# Impedance_converter.net
KiCad netlist of a schematic drawn in Altium Designer
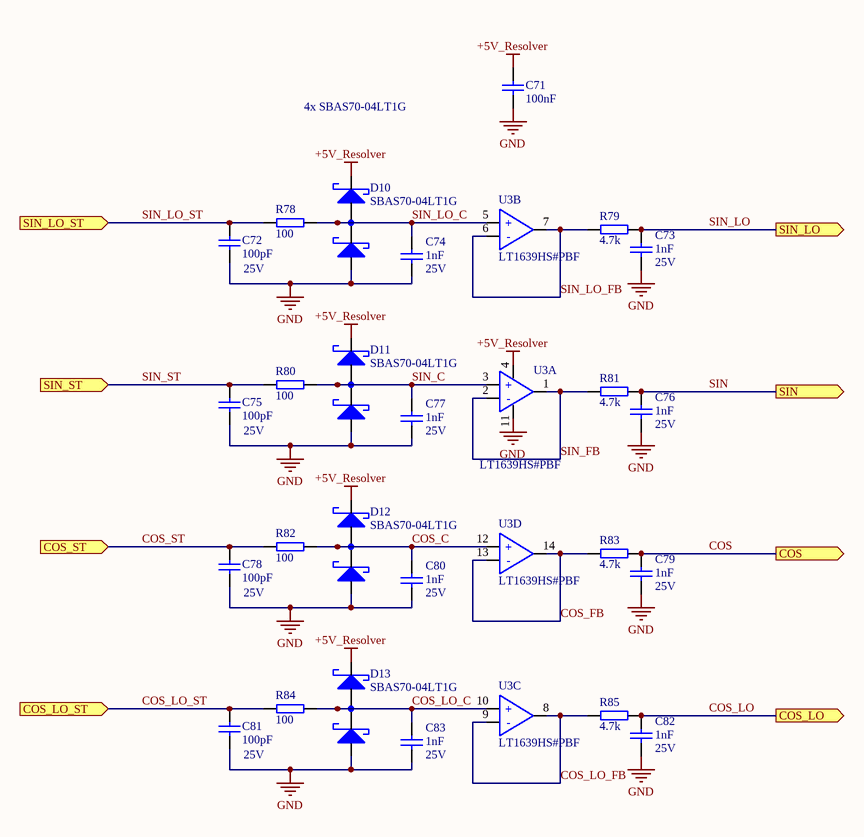
[diagram p0: Impedance converter.SchDoc]

(export (version "E")
  (design (tool "Eeschema 10.0.6"))
  (components
    (comp (ref "C71")
      (value "100nF")
      (footprint "CAPC1608X07N")
      (fields (field (name "MF") "Würth") (field (name "MPN") "885012206071") (field (name "VOLTAGE") "25V"))
      (libsource (lib "UltraZohm_ADC") (part "Cap_0603"))
    )
    (comp (ref "C72")
      (value "100pF")
      (footprint "CAPC1608X07N")
      (fields (field (name "VOLTAGE") "25V"))
      (libsource (lib "UltraZohm_ADC") (part "Cap_0603"))
    )
    (comp (ref "C73")
      (value "1nF")
      (footprint "CAPC1608X07N")
      (fields (field (name "VOLTAGE") "25V"))
      (libsource (lib "UltraZohm_ADC") (part "Cap_0603"))
    )
    (comp (ref "C74")
      (value "1nF")
      (footprint "CAPC1608X07N")
      (fields (field (name "VOLTAGE") "25V"))
      (libsource (lib "UltraZohm_ADC") (part "Cap_0603"))
    )
    (comp (ref "C75")
      (value "100pF")
      (footprint "CAPC1608X07N")
      (fields (field (name "VOLTAGE") "25V"))
      (libsource (lib "UltraZohm_ADC") (part "Cap_0603"))
    )
    (comp (ref "C76")
      (value "1nF")
      (footprint "CAPC1608X07N")
      (fields (field (name "VOLTAGE") "25V"))
      (libsource (lib "UltraZohm_ADC") (part "Cap_0603"))
    )
    (comp (ref "C77")
      (value "1nF")
      (footprint "CAPC1608X07N")
      (fields (field (name "VOLTAGE") "25V"))
      (libsource (lib "UltraZohm_ADC") (part "Cap_0603"))
    )
    (comp (ref "C78")
      (value "100pF")
      (footprint "CAPC1608X07N")
      (fields (field (name "VOLTAGE") "25V"))
      (libsource (lib "UltraZohm_ADC") (part "Cap_0603"))
    )
    (comp (ref "C79")
      (value "1nF")
      (footprint "CAPC1608X07N")
      (fields (field (name "VOLTAGE") "25V"))
      (libsource (lib "UltraZohm_ADC") (part "Cap_0603"))
    )
    (comp (ref "C80")
      (value "1nF")
      (footprint "CAPC1608X07N")
      (fields (field (name "VOLTAGE") "25V"))
      (libsource (lib "UltraZohm_ADC") (part "Cap_0603"))
    )
    (comp (ref "C81")
      (value "100pF")
      (footprint "CAPC1608X07N")
      (fields (field (name "VOLTAGE") "25V"))
      (libsource (lib "UltraZohm_ADC") (part "Cap_0603"))
    )
    (comp (ref "C82")
      (value "1nF")
      (footprint "CAPC1608X07N")
      (fields (field (name "VOLTAGE") "25V"))
      (libsource (lib "UltraZohm_ADC") (part "Cap_0603"))
    )
    (comp (ref "C83")
      (value "1nF")
      (footprint "CAPC1608X07N")
      (fields (field (name "VOLTAGE") "25V"))
      (libsource (lib "UltraZohm_ADC") (part "Cap_0603"))
    )
    (comp (ref "D10")
      (value "SBAS70-04LT1G")
      (footprint "SOT-23")
      (description "DIODE SCHOTTKY 70V DUAL SOT23")
      (fields (field (name "MF") "ON Semiconductor"))
      (libsource (lib "Componentes_SOC") (part "Diode Array Schottky"))
    )
    (comp (ref "D11")
      (value "SBAS70-04LT1G")
      (footprint "SOT-23")
      (description "DIODE SCHOTTKY 70V DUAL SOT23")
      (fields (field (name "MF") "ON Semiconductor"))
      (libsource (lib "Componentes_SOC") (part "Diode Array Schottky"))
    )
    (comp (ref "D12")
      (value "SBAS70-04LT1G")
      (footprint "SOT-23")
      (description "DIODE SCHOTTKY 70V DUAL SOT23")
      (fields (field (name "MF") "ON Semiconductor"))
      (libsource (lib "Componentes_SOC") (part "Diode Array Schottky"))
    )
    (comp (ref "D13")
      (value "SBAS70-04LT1G")
      (footprint "SOT-23")
      (description "DIODE SCHOTTKY 70V DUAL SOT23")
      (fields (field (name "MF") "ON Semiconductor"))
      (libsource (lib "Componentes_SOC") (part "Diode Array Schottky"))
    )
    (comp (ref "R78")
      (value "100")
      (footprint "RESC1608X06N")
      (libsource (lib "UltraZohm_ADC") (part "R_0603"))
    )
    (comp (ref "R79")
      (value "4.7k")
      (footprint "RESC1608X06N")
      (libsource (lib "UltraZohm_ADC") (part "R_0603"))
    )
    (comp (ref "R80")
      (value "100")
      (footprint "RESC1608X06N")
      (libsource (lib "UltraZohm_ADC") (part "R_0603"))
    )
    (comp (ref "R81")
      (value "4.7k")
      (footprint "RESC1608X06N")
      (libsource (lib "UltraZohm_ADC") (part "R_0603"))
    )
    (comp (ref "R82")
      (value "100")
      (footprint "RESC1608X06N")
      (libsource (lib "UltraZohm_ADC") (part "R_0603"))
    )
    (comp (ref "R83")
      (value "4.7k")
      (footprint "RESC1608X06N")
      (libsource (lib "UltraZohm_ADC") (part "R_0603"))
    )
    (comp (ref "R84")
      (value "100")
      (footprint "RESC1608X06N")
      (libsource (lib "UltraZohm_ADC") (part "R_0603"))
    )
    (comp (ref "R85")
      (value "4.7k")
      (footprint "RESC1608X06N")
      (libsource (lib "UltraZohm_ADC") (part "R_0603"))
    )
    (comp (ref "U3")
      (value "LT1639HS#PBF")
      (footprint "SOIC-14")
      (description "IC OPAMP GP 4 CIRCUIT 14SO")
      (fields (field (name "MF") "Analog Devices"))
      (libsource (lib "Componentes_SOC") (part "LT1639"))
    )
  )
  (nets
    (net (code "1") (name "+5V_Resolver") (class "Default")
      (node (ref "C71") (pin "1") (pinfunction "1_1") (pintype "passive"))
      (node (ref "D10") (pin "2") (pintype "passive"))
      (node (ref "D11") (pin "2") (pintype "passive"))
      (node (ref "D12") (pin "2") (pintype "passive"))
      (node (ref "D13") (pin "2") (pintype "passive"))
      (node (ref "U3") (pin "4") (pinfunction "V+_4") (pintype "passive"))
    )
    (net (code "2") (name "/COS") (class "Default")
      (node (ref "C79") (pin "1") (pinfunction "1_1") (pintype "passive"))
      (node (ref "R83") (pin "2") (pintype "passive"))
    )
    (net (code "3") (name "/COS_C") (class "Default")
      (node (ref "C80") (pin "1") (pinfunction "1_1") (pintype "passive"))
      (node (ref "D12") (pin "3") (pintype "passive"))
      (node (ref "R82") (pin "2") (pintype "passive"))
      (node (ref "U3") (pin "12") (pinfunction "+_12") (pintype "passive"))
    )
    (net (code "4") (name "/COS_FB") (class "Default")
      (node (ref "R83") (pin "1") (pintype "passive"))
      (node (ref "U3") (pin "13") (pinfunction "-_13") (pintype "passive"))
      (node (ref "U3") (pin "14") (pintype "passive"))
    )
    (net (code "5") (name "/COS_LO") (class "Default")
      (node (ref "C82") (pin "1") (pinfunction "1_1") (pintype "passive"))
      (node (ref "R85") (pin "2") (pintype "passive"))
    )
    (net (code "6") (name "/COS_LO_C") (class "Default")
      (node (ref "C83") (pin "1") (pinfunction "1_1") (pintype "passive"))
      (node (ref "D13") (pin "3") (pintype "passive"))
      (node (ref "R84") (pin "2") (pintype "passive"))
      (node (ref "U3") (pin "10") (pinfunction "+_10") (pintype "passive"))
    )
    (net (code "7") (name "/COS_LO_FB") (class "Default")
      (node (ref "R85") (pin "1") (pintype "passive"))
      (node (ref "U3") (pin "8") (pintype "passive"))
      (node (ref "U3") (pin "9") (pinfunction "-_9") (pintype "passive"))
    )
    (net (code "8") (name "/COS_LO_ST") (class "Default")
      (node (ref "C81") (pin "1") (pinfunction "1_1") (pintype "passive"))
      (node (ref "R84") (pin "1") (pintype "passive"))
    )
    (net (code "9") (name "/COS_ST") (class "Default")
      (node (ref "C78") (pin "1") (pinfunction "1_1") (pintype "passive"))
      (node (ref "R82") (pin "1") (pintype "passive"))
    )
    (net (code "10") (name "/SIN") (class "Default")
      (node (ref "C76") (pin "1") (pinfunction "1_1") (pintype "passive"))
      (node (ref "R81") (pin "2") (pintype "passive"))
    )
    (net (code "11") (name "/SIN_C") (class "Default")
      (node (ref "C77") (pin "1") (pinfunction "1_1") (pintype "passive"))
      (node (ref "D11") (pin "3") (pintype "passive"))
      (node (ref "R80") (pin "2") (pintype "passive"))
      (node (ref "U3") (pin "3") (pinfunction "+_3") (pintype "passive"))
    )
    (net (code "12") (name "/SIN_FB") (class "Default")
      (node (ref "R81") (pin "1") (pintype "passive"))
      (node (ref "U3") (pin "1") (pintype "passive"))
      (node (ref "U3") (pin "2") (pinfunction "-_2") (pintype "passive"))
    )
    (net (code "13") (name "/SIN_LO") (class "Default")
      (node (ref "C73") (pin "1") (pinfunction "1_1") (pintype "passive"))
      (node (ref "R79") (pin "2") (pintype "passive"))
    )
    (net (code "14") (name "/SIN_LO_C") (class "Default")
      (node (ref "C74") (pin "1") (pinfunction "1_1") (pintype "passive"))
      (node (ref "D10") (pin "3") (pintype "passive"))
      (node (ref "R78") (pin "2") (pintype "passive"))
      (node (ref "U3") (pin "5") (pinfunction "+_5") (pintype "passive"))
    )
    (net (code "15") (name "/SIN_LO_FB") (class "Default")
      (node (ref "R79") (pin "1") (pintype "passive"))
      (node (ref "U3") (pin "6") (pinfunction "-_6") (pintype "passive"))
      (node (ref "U3") (pin "7") (pintype "passive"))
    )
    (net (code "16") (name "/SIN_LO_ST") (class "Default")
      (node (ref "C72") (pin "1") (pinfunction "1_1") (pintype "passive"))
      (node (ref "R78") (pin "1") (pintype "passive"))
    )
    (net (code "17") (name "/SIN_ST") (class "Default")
      (node (ref "C75") (pin "1") (pinfunction "1_1") (pintype "passive"))
      (node (ref "R80") (pin "1") (pintype "passive"))
    )
    (net (code "18") (name "GND") (class "Default")
      (node (ref "C71") (pin "2") (pinfunction "2_2") (pintype "passive"))
      (node (ref "C72") (pin "2") (pinfunction "2_2") (pintype "passive"))
      (node (ref "C73") (pin "2") (pinfunction "2_2") (pintype "passive"))
      (node (ref "C74") (pin "2") (pinfunction "2_2") (pintype "passive"))
      (node (ref "C75") (pin "2") (pinfunction "2_2") (pintype "passive"))
      (node (ref "C76") (pin "2") (pinfunction "2_2") (pintype "passive"))
      (node (ref "C77") (pin "2") (pinfunction "2_2") (pintype "passive"))
      (node (ref "C78") (pin "2") (pinfunction "2_2") (pintype "passive"))
      (node (ref "C79") (pin "2") (pinfunction "2_2") (pintype "passive"))
      (node (ref "C80") (pin "2") (pinfunction "2_2") (pintype "passive"))
      (node (ref "C81") (pin "2") (pinfunction "2_2") (pintype "passive"))
      (node (ref "C82") (pin "2") (pinfunction "2_2") (pintype "passive"))
      (node (ref "C83") (pin "2") (pinfunction "2_2") (pintype "passive"))
      (node (ref "D10") (pin "1") (pintype "passive"))
      (node (ref "D11") (pin "1") (pintype "passive"))
      (node (ref "D12") (pin "1") (pintype "passive"))
      (node (ref "D13") (pin "1") (pintype "passive"))
      (node (ref "U3") (pin "11") (pinfunction "V-_11") (pintype "passive"))
    )
  )
)
